# SCH_H-brug_Jao.net
KiCad netlist of a schematic drawn in EasyEDA
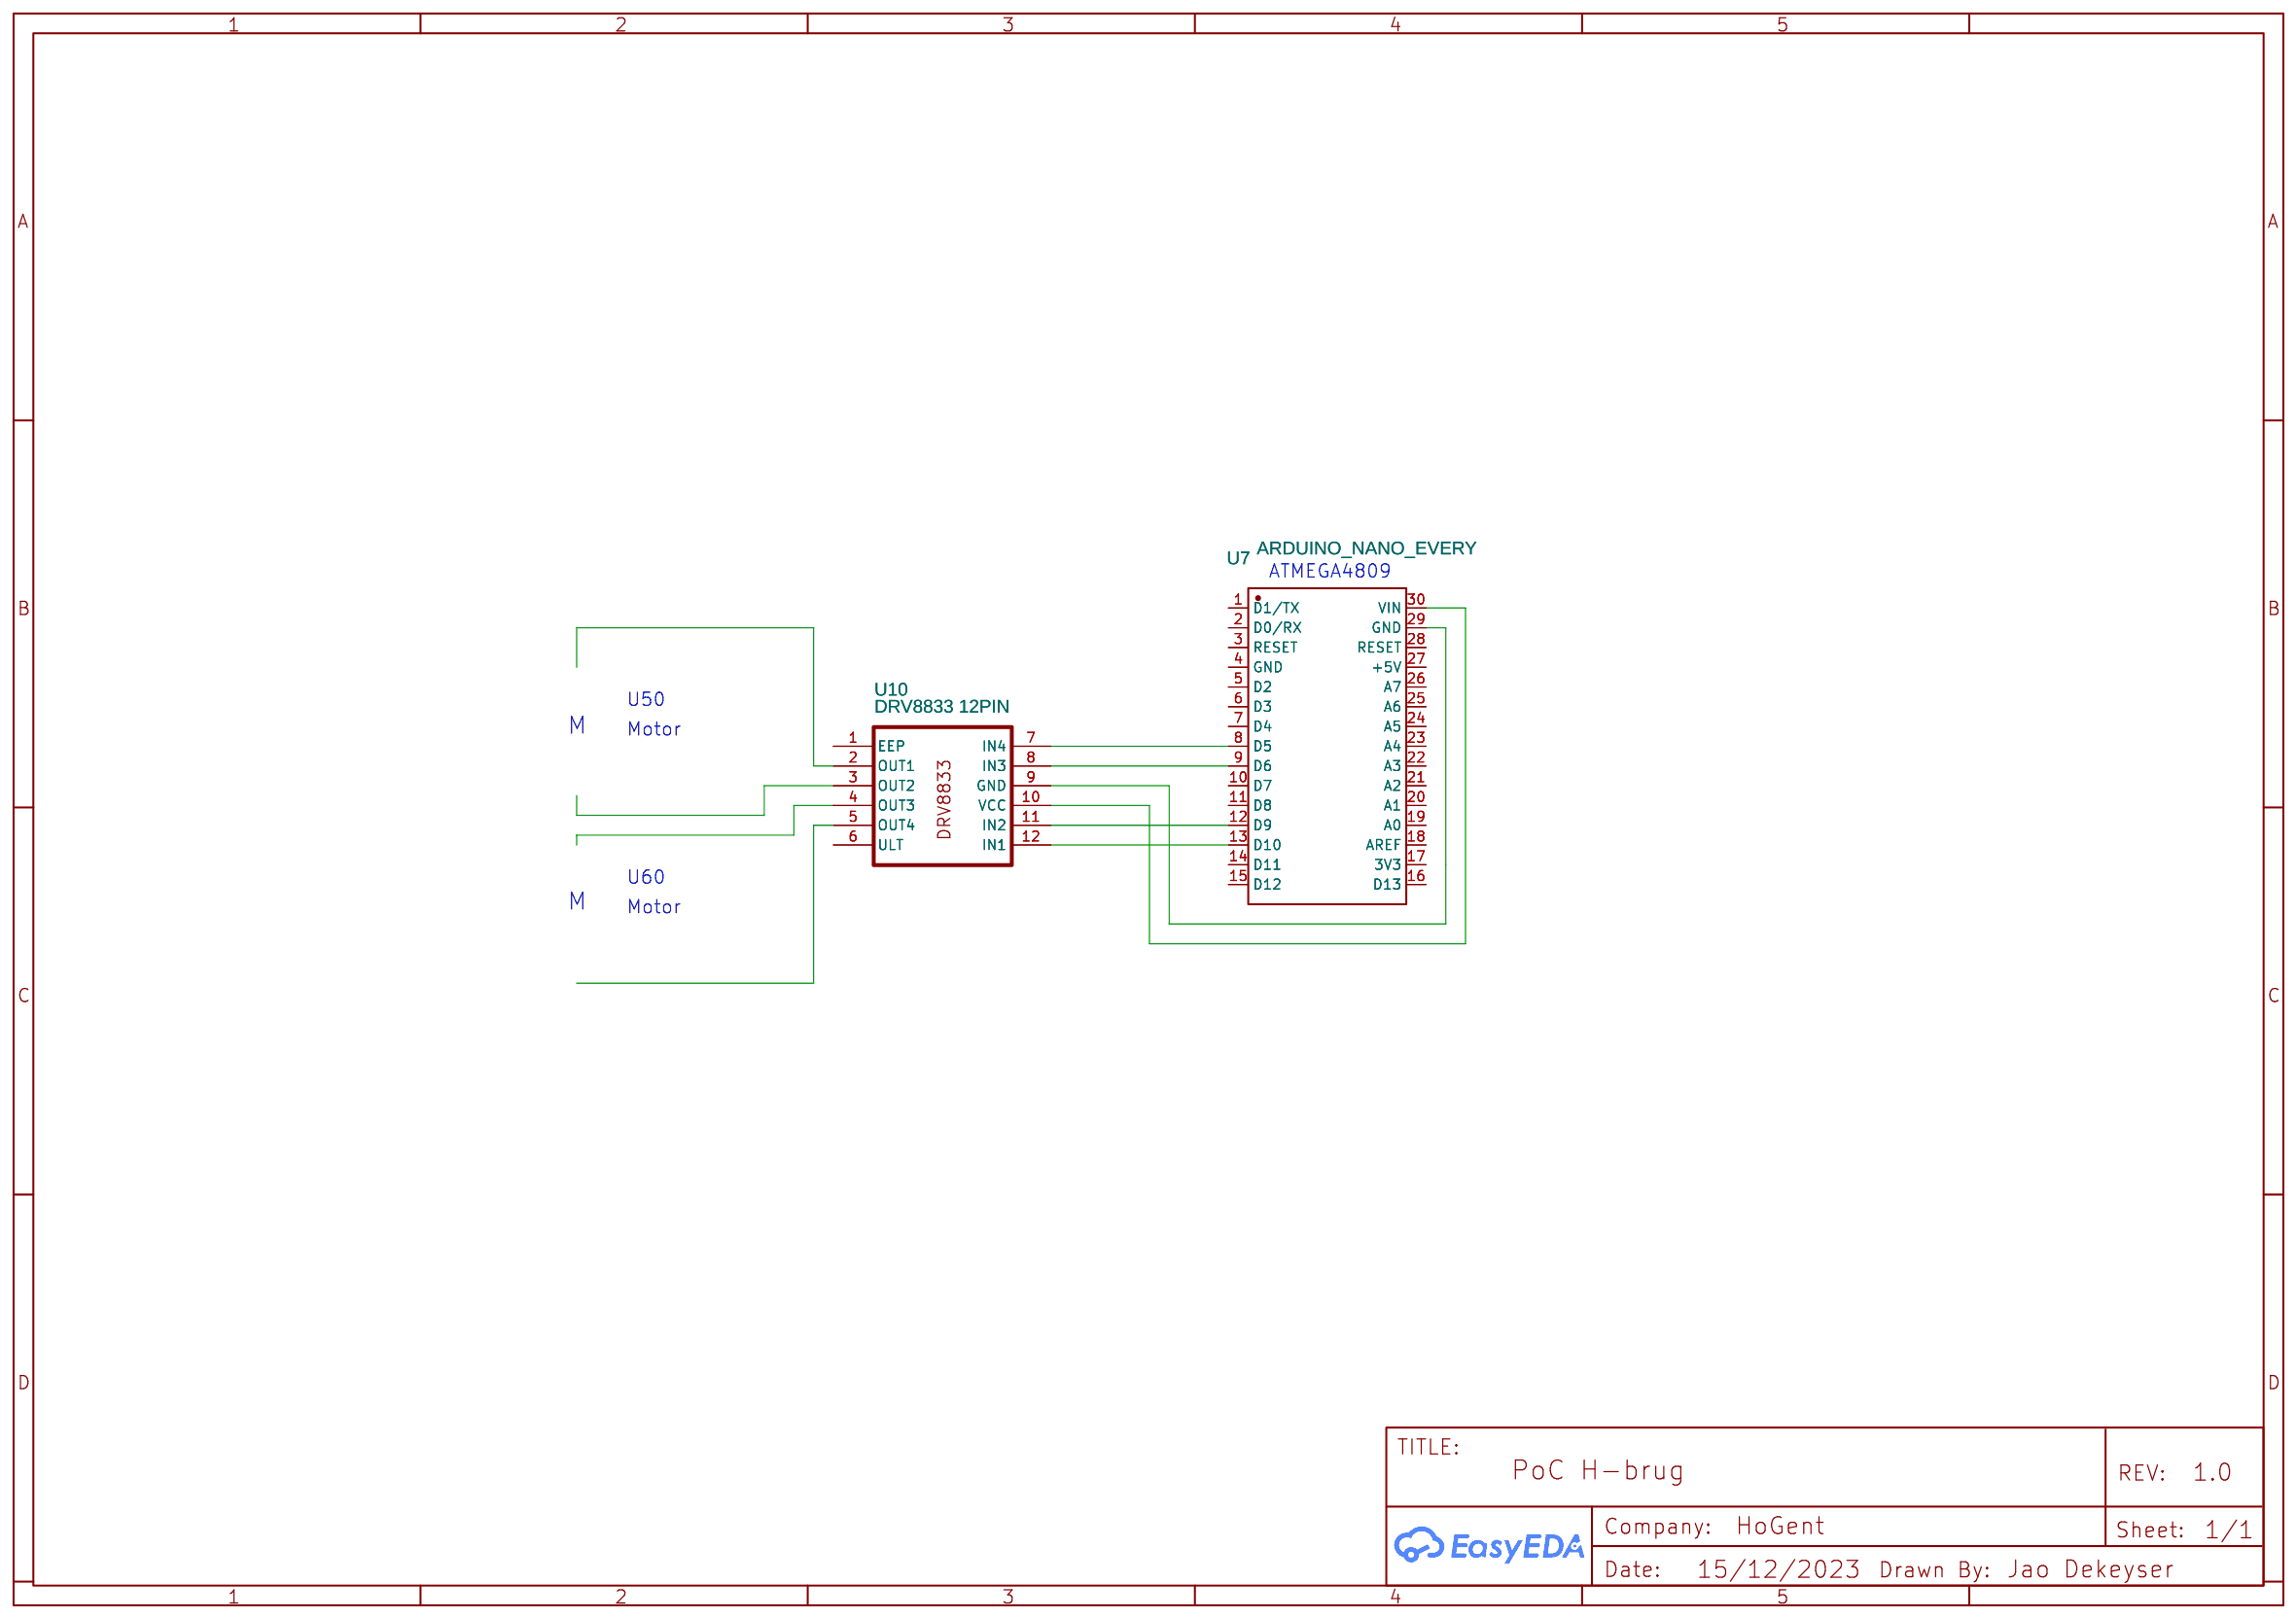
[diagram p0: schematic sheet]

(export (version "E")
  (design (tool "Eeschema 10.0.6"))
  (components
    (comp (ref "U7")
      (value "ARDUINO_NANO_EVERY")
      (fields (field (name "Manufacturer Part") "ARDUINO_NANO"))
      (libsource (lib "") (part "ARDUINO_NANO"))
    )
    (comp (ref "U10") (value "DRV8833 12PIN") (libsource (lib "") (part "DRV8833 12PIN")))
  )
  (nets
    (net (code "1") (name "Net-(U10-GND)") (class "Default")
      (node (ref "U10") (pin "9") (pinfunction "GND_9") (pintype "unspecified"))
      (node (ref "U7") (pin "29") (pinfunction "GND_29") (pintype "unspecified"))
    )
    (net (code "2") (name "Net-(U10-IN1)") (class "Default")
      (node (ref "U10") (pin "12") (pinfunction "IN1_12") (pintype "unspecified"))
      (node (ref "U7") (pin "13") (pinfunction "D10_13") (pintype "unspecified"))
    )
    (net (code "3") (name "Net-(U10-IN2)") (class "Default")
      (node (ref "U10") (pin "11") (pinfunction "IN2_11") (pintype "unspecified"))
      (node (ref "U7") (pin "12") (pinfunction "D9_12") (pintype "unspecified"))
    )
    (net (code "4") (name "Net-(U10-IN3)") (class "Default")
      (node (ref "U10") (pin "8") (pinfunction "IN3_8") (pintype "unspecified"))
      (node (ref "U7") (pin "9") (pinfunction "D6_9") (pintype "unspecified"))
    )
    (net (code "5") (name "Net-(U10-IN4)") (class "Default")
      (node (ref "U10") (pin "7") (pinfunction "IN4_7") (pintype "unspecified"))
      (node (ref "U7") (pin "8") (pinfunction "D5_8") (pintype "unspecified"))
    )
    (net (code "6") (name "Net-(U10-VCC)") (class "Default")
      (node (ref "U10") (pin "10") (pinfunction "VCC_10") (pintype "unspecified"))
      (node (ref "U7") (pin "30") (pinfunction "VIN_30") (pintype "unspecified"))
    )
    (net (code "7") (name "unconnected-(U7-+5V-Pad27)") (class "Default")
      (node (ref "U7") (pin "27") (pinfunction "+5V_27") (pintype "unspecified"))
    )
    (net (code "8") (name "unconnected-(U7-3V3-Pad17)") (class "Default")
      (node (ref "U7") (pin "17") (pinfunction "3V3_17") (pintype "unspecified"))
    )
    (net (code "9") (name "unconnected-(U7-A0-Pad19)") (class "Default")
      (node (ref "U7") (pin "19") (pinfunction "A0_19") (pintype "unspecified"))
    )
    (net (code "10") (name "unconnected-(U7-A1-Pad20)") (class "Default")
      (node (ref "U7") (pin "20") (pinfunction "A1_20") (pintype "unspecified"))
    )
    (net (code "11") (name "unconnected-(U7-A2-Pad21)") (class "Default")
      (node (ref "U7") (pin "21") (pinfunction "A2_21") (pintype "unspecified"))
    )
    (net (code "12") (name "unconnected-(U7-A3-Pad22)") (class "Default")
      (node (ref "U7") (pin "22") (pinfunction "A3_22") (pintype "unspecified"))
    )
    (net (code "13") (name "unconnected-(U7-A4-Pad23)") (class "Default")
      (node (ref "U7") (pin "23") (pinfunction "A4_23") (pintype "unspecified"))
    )
    (net (code "14") (name "unconnected-(U7-A5-Pad24)") (class "Default")
      (node (ref "U7") (pin "24") (pinfunction "A5_24") (pintype "unspecified"))
    )
    (net (code "15") (name "unconnected-(U7-A6-Pad25)") (class "Default")
      (node (ref "U7") (pin "25") (pinfunction "A6_25") (pintype "unspecified"))
    )
    (net (code "16") (name "unconnected-(U7-A7-Pad26)") (class "Default")
      (node (ref "U7") (pin "26") (pinfunction "A7_26") (pintype "unspecified"))
    )
    (net (code "17") (name "unconnected-(U7-AREF-Pad18)") (class "Default")
      (node (ref "U7") (pin "18") (pinfunction "AREF_18") (pintype "unspecified"))
    )
    (net (code "18") (name "unconnected-(U7-D0{slash}RX-Pad2)") (class "Default")
      (node (ref "U7") (pin "2") (pinfunction "D0/RX_2") (pintype "unspecified"))
    )
    (net (code "19") (name "unconnected-(U7-D1{slash}TX-Pad1)") (class "Default")
      (node (ref "U7") (pin "1") (pinfunction "D1/TX_1") (pintype "unspecified"))
    )
    (net (code "20") (name "unconnected-(U7-D2-Pad5)") (class "Default")
      (node (ref "U7") (pin "5") (pinfunction "D2_5") (pintype "unspecified"))
    )
    (net (code "21") (name "unconnected-(U7-D3-Pad6)") (class "Default")
      (node (ref "U7") (pin "6") (pinfunction "D3_6") (pintype "unspecified"))
    )
    (net (code "22") (name "unconnected-(U7-D4-Pad7)") (class "Default")
      (node (ref "U7") (pin "7") (pinfunction "D4_7") (pintype "unspecified"))
    )
    (net (code "23") (name "unconnected-(U7-D7-Pad10)") (class "Default")
      (node (ref "U7") (pin "10") (pinfunction "D7_10") (pintype "unspecified"))
    )
    (net (code "24") (name "unconnected-(U7-D8-Pad11)") (class "Default")
      (node (ref "U7") (pin "11") (pinfunction "D8_11") (pintype "unspecified"))
    )
    (net (code "25") (name "unconnected-(U7-D11-Pad14)") (class "Default")
      (node (ref "U7") (pin "14") (pinfunction "D11_14") (pintype "unspecified"))
    )
    (net (code "26") (name "unconnected-(U7-D12-Pad15)") (class "Default")
      (node (ref "U7") (pin "15") (pinfunction "D12_15") (pintype "unspecified"))
    )
    (net (code "27") (name "unconnected-(U7-D13-Pad16)") (class "Default")
      (node (ref "U7") (pin "16") (pinfunction "D13_16") (pintype "unspecified"))
    )
    (net (code "28") (name "unconnected-(U7-GND-Pad4)") (class "Default")
      (node (ref "U7") (pin "4") (pinfunction "GND_4") (pintype "unspecified"))
    )
    (net (code "29") (name "unconnected-(U7-RESET-Pad3)") (class "Default")
      (node (ref "U7") (pin "3") (pinfunction "RESET_3") (pintype "unspecified"))
    )
    (net (code "30") (name "unconnected-(U7-RESET-Pad28)") (class "Default")
      (node (ref "U7") (pin "28") (pinfunction "RESET_28") (pintype "unspecified"))
    )
    (net (code "31") (name "unconnected-(U10-EEP-Pad1)") (class "Default")
      (node (ref "U10") (pin "1") (pinfunction "EEP_1") (pintype "unspecified"))
    )
    (net (code "32") (name "unconnected-(U10-OUT1-Pad2)") (class "Default")
      (node (ref "U10") (pin "2") (pinfunction "OUT1_2") (pintype "unspecified"))
    )
    (net (code "33") (name "unconnected-(U10-OUT2-Pad3)") (class "Default")
      (node (ref "U10") (pin "3") (pinfunction "OUT2_3") (pintype "unspecified"))
    )
    (net (code "34") (name "unconnected-(U10-OUT3-Pad4)") (class "Default")
      (node (ref "U10") (pin "4") (pinfunction "OUT3_4") (pintype "unspecified"))
    )
    (net (code "35") (name "unconnected-(U10-OUT4-Pad5)") (class "Default")
      (node (ref "U10") (pin "5") (pinfunction "OUT4_5") (pintype "unspecified"))
    )
    (net (code "36") (name "unconnected-(U10-ULT-Pad6)") (class "Default")
      (node (ref "U10") (pin "6") (pinfunction "ULT_6") (pintype "unspecified"))
    )
  )
)
